# ControlC.net
KiCad netlist of a schematic drawn in EAGLE
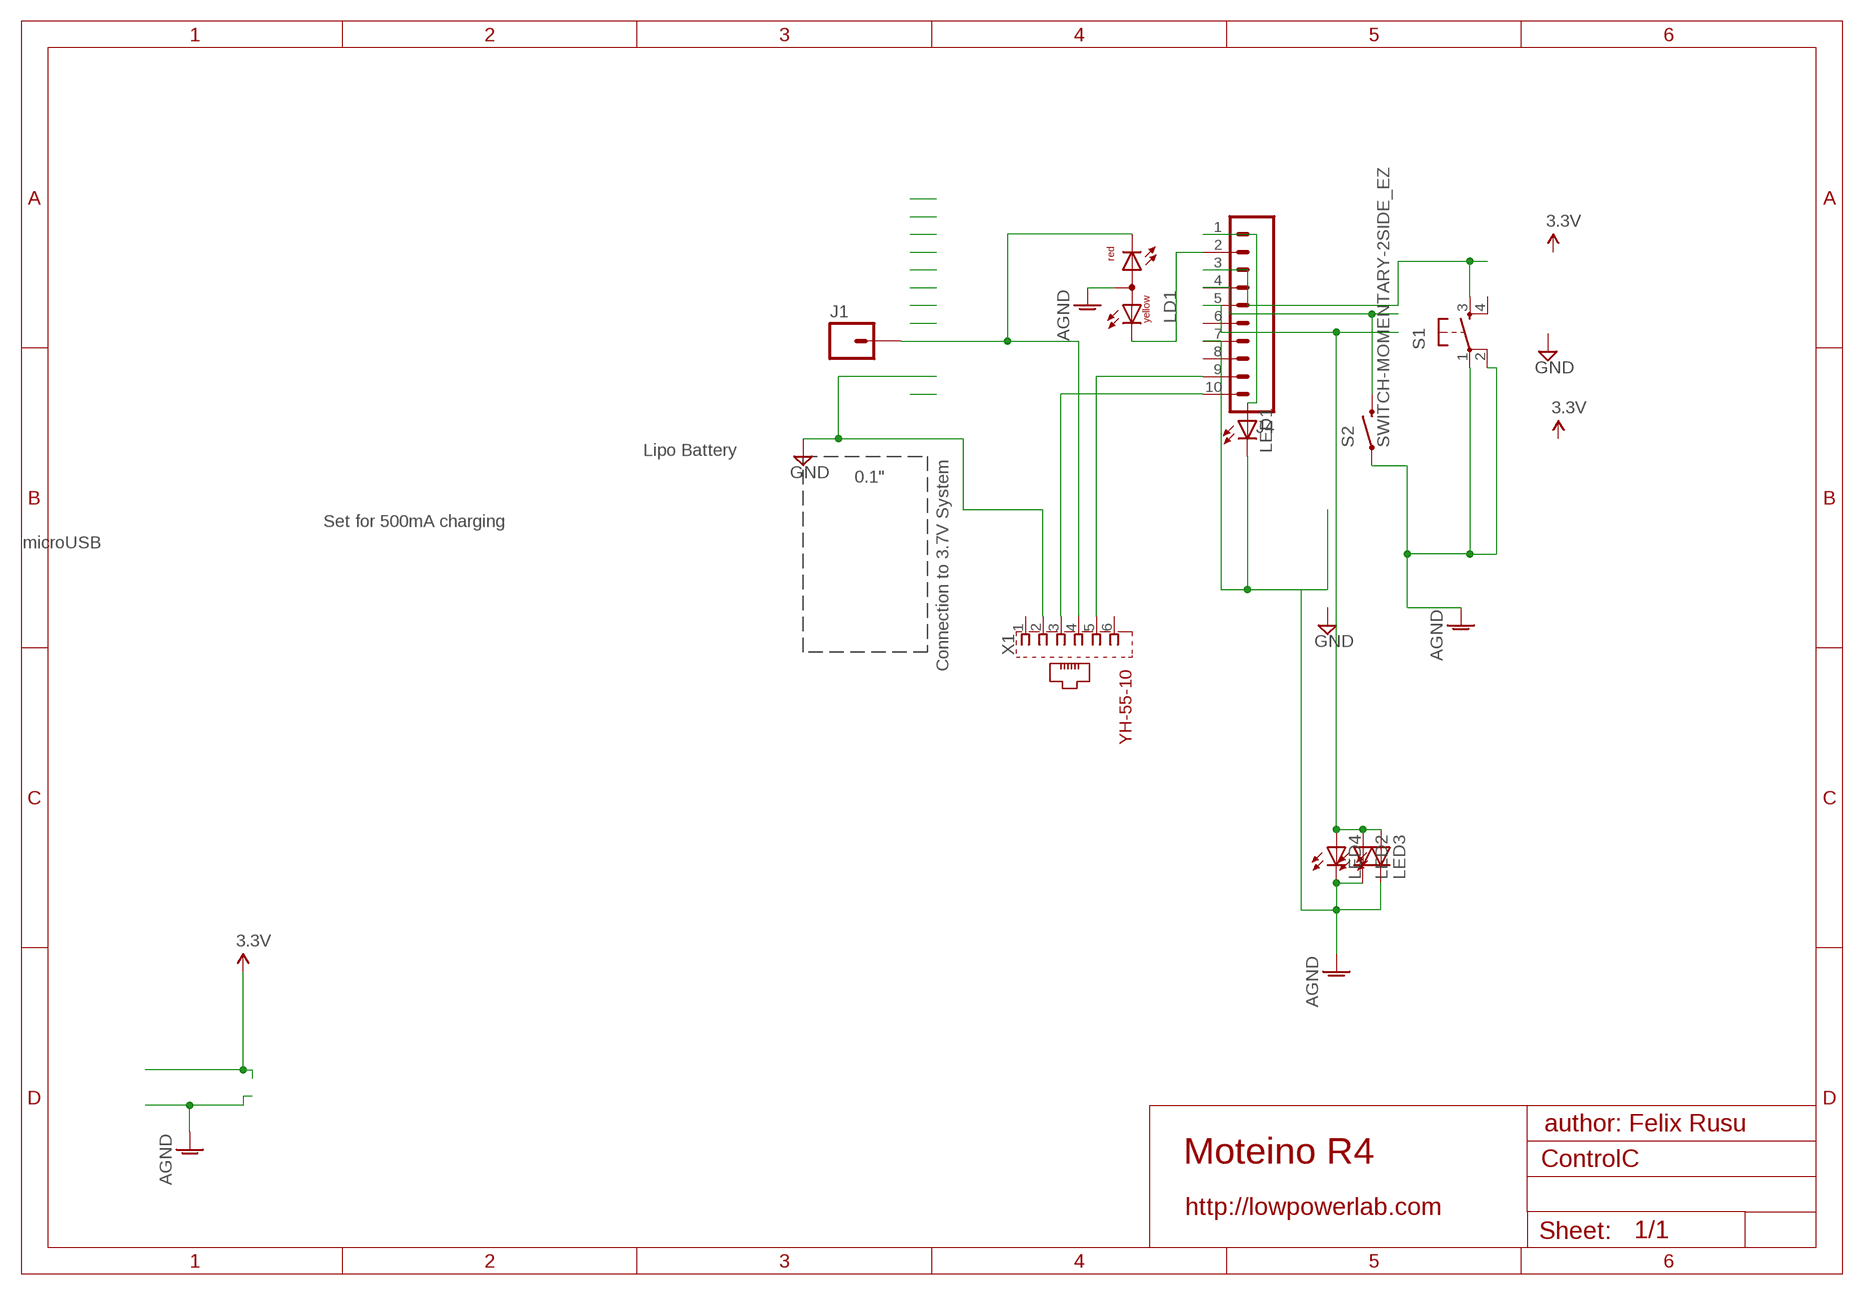
[diagram p0: schematic, sheet 1]

(export (version "E")
  (design (tool "Eeschema 10.0.6"))
  (components
    (comp (ref "J1")
      (value "M01PTH")
      (footprint "eagle-import:1X01")
      (libsource (lib "eagle-import") (part "M01PTH"))
    )
    (comp (ref "J4")
      (value "M10SILK_FEMALE_PTH")
      (footprint "eagle-import:1X10")
      (libsource (lib "eagle-import") (part "M10SILK_FEMALE_PTH"))
    )
    (comp (ref "LD1")
      (value "DUOLED-RY-A")
      (footprint "eagle-import:DUOLED-A-5MM")
      (libsource (lib "eagle-import") (part "DUOLED-RY-A"))
    )
    (comp (ref "LED1")
      (value "LED3MM")
      (footprint "eagle-import:LED3MM")
      (libsource (lib "eagle-import") (part "LED3MM"))
    )
    (comp (ref "LED2")
      (value "LED3MM")
      (footprint "eagle-import:LED3MM")
      (libsource (lib "eagle-import") (part "LED3MM"))
    )
    (comp (ref "LED3")
      (value "LED3MM")
      (footprint "eagle-import:LED3MM")
      (libsource (lib "eagle-import") (part "LED3MM"))
    )
    (comp (ref "LED4")
      (value "LED3MM")
      (footprint "eagle-import:LED3MM")
      (libsource (lib "eagle-import") (part "LED3MM"))
    )
    (comp (ref "S1")
      (value "TAC_SWITCHPTH")
      (footprint "eagle-import:TACTILE-PTH")
      (libsource (lib "eagle-import") (part "TAC_SWITCHPTH"))
    )
    (comp (ref "S2")
      (value "SWITCH-MOMENTARY-2SIDE_EZ")
      (footprint "eagle-import:TACTILE-PTH-SIDEEZ")
      (libsource (lib "eagle-import") (part "SWITCH-MOMENTARY-2SIDE_EZ"))
    )
    (comp (ref "X1")
      (value "YH-55-10")
      (footprint "eagle-import:YH-55-10")
      (libsource (lib "eagle-import") (part "YH-55-10"))
    )
  )
  (nets
    (net (code "2") (name "AGND") (class "Default")
      (node (ref "J4") (pin "7") (pinfunction "7_7") (pintype "passive"))
      (node (ref "LD1") (pin "A") (pinfunction "A_A") (pintype "passive"))
      (node (ref "LED1") (pin "K") (pinfunction "C_K") (pintype "passive"))
      (node (ref "LED2") (pin "K") (pinfunction "C_K") (pintype "passive"))
      (node (ref "LED3") (pin "K") (pinfunction "C_K") (pintype "passive"))
      (node (ref "LED4") (pin "K") (pinfunction "C_K") (pintype "passive"))
      (node (ref "S1") (pin "1") (pinfunction "1_1") (pintype "passive"))
      (node (ref "S1") (pin "2") (pinfunction "2_2") (pintype "passive"))
      (node (ref "S2") (pin "1") (pinfunction "1_1") (pintype "passive"))
    )
    (net (code "3") (name "GND") (class "Default")
      (node (ref "X1") (pin "2") (pinfunction "2_2") (pintype "passive"))
    )
    (net (code "4") (name "Net-(J1-Pad1)") (class "Default")
      (node (ref "J1") (pin "1") (pinfunction "1_1") (pintype "passive"))
      (node (ref "LD1") (pin "CR") (pinfunction "CR_CR") (pintype "passive"))
      (node (ref "X1") (pin "4") (pinfunction "4_4") (pintype "passive"))
    )
    (net (code "5") (name "Net-(J4-Pad1)") (class "Default")
      (node (ref "J4") (pin "1") (pinfunction "1_1") (pintype "passive"))
      (node (ref "LED1") (pin "A") (pinfunction "A_A") (pintype "passive"))
    )
    (net (code "6") (name "Net-(J4-Pad3)") (class "Default")
      (node (ref "J4") (pin "3") (pinfunction "3_3") (pintype "passive"))
      (node (ref "S1") (pin "3") (pinfunction "3_3") (pintype "passive"))
    )
    (net (code "7") (name "Net-(J4-Pad4)") (class "Default")
      (node (ref "J4") (pin "4") (pinfunction "4_4") (pintype "passive"))
      (node (ref "S2") (pin "2") (pinfunction "2_2") (pintype "passive"))
    )
    (net (code "8") (name "Net-(J4-Pad5)") (class "Default")
      (node (ref "J4") (pin "5") (pinfunction "5_5") (pintype "passive"))
      (node (ref "LED2") (pin "A") (pinfunction "A_A") (pintype "passive"))
      (node (ref "LED3") (pin "A") (pinfunction "A_A") (pintype "passive"))
      (node (ref "LED4") (pin "A") (pinfunction "A_A") (pintype "passive"))
    )
    (net (code "9") (name "Net-(J4-Pad9)") (class "Default")
      (node (ref "J4") (pin "9") (pinfunction "9_9") (pintype "passive"))
      (node (ref "X1") (pin "5") (pinfunction "5_5") (pintype "passive"))
    )
    (net (code "10") (name "Net-(J4-Pad10)") (class "Default")
      (node (ref "J4") (pin "10") (pinfunction "10_10") (pintype "passive"))
      (node (ref "X1") (pin "3") (pinfunction "3_3") (pintype "passive"))
    )
    (net (code "11") (name "Net-(LD1-CY)") (class "Default")
      (node (ref "J4") (pin "2") (pinfunction "2_2") (pintype "passive"))
      (node (ref "LD1") (pin "CX") (pinfunction "CY_CX") (pintype "passive"))
    )
    (net (code "12") (name "unconnected-(J4-Pad6)") (class "Default")
      (node (ref "J4") (pin "6") (pinfunction "6_6") (pintype "passive"))
    )
    (net (code "13") (name "unconnected-(J4-Pad8)") (class "Default")
      (node (ref "J4") (pin "8") (pinfunction "8_8") (pintype "passive"))
    )
    (net (code "14") (name "unconnected-(S1-Pad4)") (class "Default")
      (node (ref "S1") (pin "4") (pinfunction "4_4") (pintype "passive"))
    )
    (net (code "15") (name "unconnected-(X1-Pad1)") (class "Default")
      (node (ref "X1") (pin "1") (pinfunction "1_1") (pintype "passive"))
    )
    (net (code "16") (name "unconnected-(X1-Pad6)") (class "Default")
      (node (ref "X1") (pin "6") (pinfunction "6_6") (pintype "passive"))
    )
  )
)
